# 2S_BATTERY_PROTECTION_SCH.net
KiCad netlist of a schematic drawn in Altium Designer
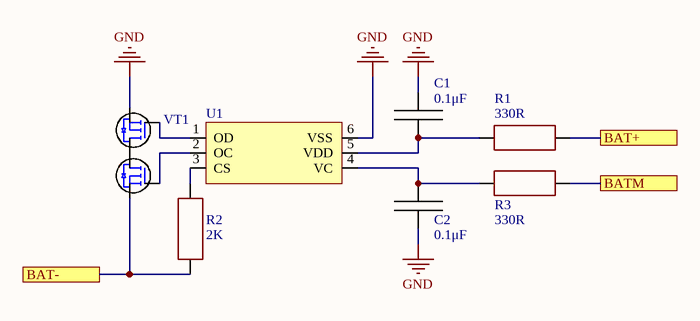
[diagram p0: 2S_BATTERY_PROTECTION_SCH.SchDoc]

(export (version "E")
  (design (tool "Eeschema 10.0.6"))
  (components
    (comp (ref "C1")
      (value "0.1μF")
      (footprint "CAP: 0402")
      (fields (field (name "VOLTAGE") "??V") (field (name "Comment") "Cap_0402"))
      (libsource (lib "capacitor") (part "Cap_0402"))
    )
    (comp (ref "C2")
      (value "0.1μF")
      (footprint "CAP: 0402")
      (fields (field (name "VOLTAGE") "??V") (field (name "Comment") "Cap_0402"))
      (libsource (lib "capacitor") (part "Cap_0402"))
    )
    (comp (ref "R1")
      (value "330R")
      (footprint "standard-case:RES: 0402")
      (fields (field (name "TOLERANCE") "±5%"))
      (libsource (lib "") (part "Resistor_0402_1"))
    )
    (comp (ref "R2")
      (value "2K")
      (footprint "standard-case:RES: 0402")
      (fields (field (name "TOLERANCE") "±5%"))
      (libsource (lib "resistor") (part "Resistor_0402"))
    )
    (comp (ref "R3")
      (value "330R")
      (footprint "standard-case:RES: 0402")
      (fields (field (name "TOLERANCE") "±5%"))
      (libsource (lib "") (part "Resistor_0402_1"))
    )
    (comp (ref "U1")
      (value "HY2120")
      (footprint "SOT-23-6")
      (description "2-cell lithium-ion/lithium polymer rechargeable battery\r\nprotection")
      (fields (field (name "MANUFACTURER") "HYCON"))
      (libsource (lib "MY_INT_LIB") (part "HY2120"))
    )
    (comp (ref "VT1")
      (value "8205A")
      (footprint "SOT-23-6")
      (description "MOSFET N-CHANNEL 20V 5A")
      (fields (field (name "MANUFACTURER") "UMW"))
      (libsource (lib "MY_INT_LIB") (part "8205A"))
    )
  )
  (nets
    (net (code "1") (name "/BAT+") (class "Default")
      (node (ref "R1") (pin "2") (pinfunction "2_2") (pintype "passive"))
    )
    (net (code "2") (name "/BAT-") (class "Default")
      (node (ref "R2") (pin "1") (pinfunction "1_1") (pintype "passive"))
      (node (ref "VT1") (pin "3") (pintype "power_in"))
    )
    (net (code "3") (name "/BATM") (class "Default")
      (node (ref "R3") (pin "2") (pinfunction "2_2") (pintype "passive"))
    )
    (net (code "4") (name "GND") (class "Default")
      (node (ref "C1") (pin "2") (pinfunction "2_2") (pintype "passive"))
      (node (ref "C2") (pin "1") (pinfunction "1_1") (pintype "passive"))
      (node (ref "U1") (pin "6") (pinfunction "VSS_6") (pintype "passive"))
      (node (ref "VT1") (pin "1") (pintype "power_in"))
    )
    (net (code "5") (name "Net-(U1-CS)") (class "Default")
      (node (ref "R2") (pin "2") (pinfunction "2_2") (pintype "passive"))
      (node (ref "U1") (pin "3") (pinfunction "CS_3") (pintype "passive"))
    )
    (net (code "6") (name "Net-(U1-OC)") (class "Default")
      (node (ref "U1") (pin "2") (pinfunction "OC_2") (pintype "passive"))
      (node (ref "VT1") (pin "4") (pintype "power_in"))
    )
    (net (code "7") (name "Net-(U1-OD)") (class "Default")
      (node (ref "U1") (pin "1") (pinfunction "OD_1") (pintype "passive"))
      (node (ref "VT1") (pin "6") (pintype "power_in"))
    )
    (net (code "8") (name "Net-(U1-VC)") (class "Default")
      (node (ref "C2") (pin "2") (pinfunction "2_2") (pintype "passive"))
      (node (ref "R3") (pin "1") (pinfunction "1_1") (pintype "passive"))
      (node (ref "U1") (pin "4") (pinfunction "VC_4") (pintype "passive"))
    )
    (net (code "9") (name "Net-(U1-VDD)") (class "Default")
      (node (ref "C1") (pin "1") (pinfunction "1_1") (pintype "passive"))
      (node (ref "R1") (pin "1") (pinfunction "1_1") (pintype "passive"))
      (node (ref "U1") (pin "5") (pinfunction "VDD_5") (pintype "passive"))
    )
    (net (code "10") (name "Net-(VT1-Pad2)") (class "Default")
      (node (ref "VT1") (pin "2") (pintype "power_in"))
      (node (ref "VT1") (pin "5") (pintype "power_in"))
    )
  )
)
